# Can-Shield.net
KiCad netlist of a schematic drawn in Altium Designer
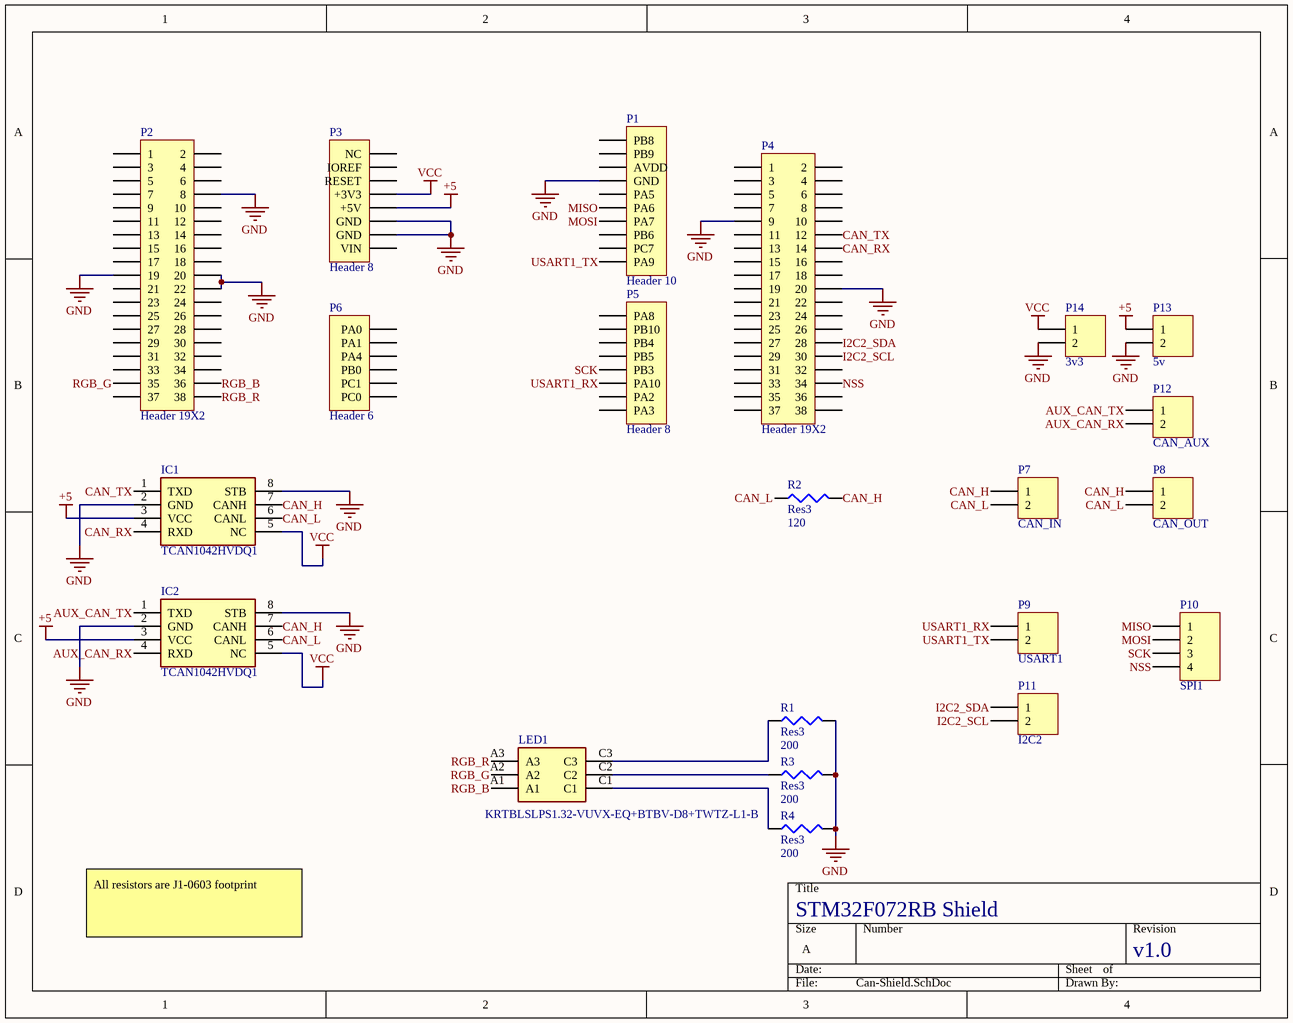
[diagram p0: Can-Shield.SchDoc]

(export (version "E")
  (design (tool "Eeschema 10.0.6"))
  (components
    (comp (ref "IC1")
      (value "TCAN1042HVDQ1")
      (footprint "SamacSys:SOIC127P600X175-8N")
      (description "Integrated Circuit")
      (fields (field (name "MOUSER PART NUMBER") "595-TCAN1042HVDQ1"))
      (libsource (lib "*") (part "TCAN1042HVDQ1"))
    )
    (comp (ref "IC2")
      (value "TCAN1042HVDQ1")
      (footprint "SamacSys:SOIC127P600X175-8N")
      (description "Integrated Circuit")
      (fields (field (name "MOUSER PART NUMBER") "595-TCAN1042HVDQ1"))
      (libsource (lib "*") (part "TCAN1042HVDQ1"))
    )
    (comp (ref "LED1")
      (value "KRTBLSLPS1.32-VUVX-EQ+BTBV-D8+TWTZ-L1-B")
      (footprint "SamacSys:KRTBLSLPS132VUVXEQBTBVD8TWTZL1B")
      (description "LED")
      (fields (field (name "MOUSER PART NUMBER") "720-KRTBLSLPS13A0062"))
      (libsource (lib "*") (part "KRTBLSLPS1.32-VUVX-EQ+BTBV-D8+TWTZ-L1-B"))
    )
    (comp (ref "P1")
      (value "Header 10")
      (footprint "HDR1X10")
      (description "Header, 10-Pin")
      (fields (field (name "PUBLISHER") "Altium Limited"))
      (libsource (lib "Miscellaneous Connectors") (part "Header 10"))
    )
    (comp (ref "P2")
      (value "Header 19X2")
      (footprint "HDR2X19")
      (description "Header, 19-Pin, Dual row")
      (fields (field (name "PUBLISHER") "Altium Limited"))
      (libsource (lib "Miscellaneous Connectors") (part "Header 19X2"))
    )
    (comp (ref "P3")
      (value "Header 8")
      (footprint "HDR1X8")
      (description "Header, 8-Pin")
      (fields (field (name "PUBLISHER") "Altium Limited"))
      (libsource (lib "Miscellaneous Connectors") (part "Header 8"))
    )
    (comp (ref "P4")
      (value "Header 19X2")
      (footprint "HDR2X19")
      (description "Header, 19-Pin, Dual row")
      (fields (field (name "PUBLISHER") "Altium Limited"))
      (libsource (lib "Miscellaneous Connectors") (part "Header 19X2"))
    )
    (comp (ref "P5")
      (value "Header 8")
      (footprint "HDR1X8")
      (description "Header, 8-Pin")
      (fields (field (name "PUBLISHER") "Altium Limited"))
      (libsource (lib "") (part "Header 8_1"))
    )
    (comp (ref "P6")
      (value "Header 6")
      (footprint "HDR1X6")
      (description "Header, 6-Pin")
      (fields (field (name "PUBLISHER") "Altium Limited"))
      (libsource (lib "Miscellaneous Connectors") (part "Header 6"))
    )
    (comp (ref "P7")
      (value "CAN_IN")
      (footprint "HDR1X2")
      (description "Header, 2-Pin")
      (fields (field (name "PUBLISHER") "Altium Limited"))
      (libsource (lib "Miscellaneous Connectors") (part "Header 2"))
    )
    (comp (ref "P8")
      (value "CAN_OUT")
      (footprint "HDR1X2")
      (description "Header, 2-Pin")
      (fields (field (name "PUBLISHER") "Altium Limited"))
      (libsource (lib "Miscellaneous Connectors") (part "Header 2"))
    )
    (comp (ref "P9")
      (value "USART1")
      (footprint "HDR1X2")
      (description "Header, 2-Pin")
      (fields (field (name "PUBLISHER") "Altium Limited"))
      (libsource (lib "Miscellaneous Connectors") (part "Header 2"))
    )
    (comp (ref "P10")
      (value "SPI1")
      (footprint "HDR1X4")
      (description "Header, 4-Pin")
      (fields (field (name "PUBLISHER") "Altium Limited"))
      (libsource (lib "Miscellaneous Connectors") (part "Header 4"))
    )
    (comp (ref "P11")
      (value "I2C2")
      (footprint "HDR1X2")
      (description "Header, 2-Pin")
      (fields (field (name "PUBLISHER") "Altium Limited"))
      (libsource (lib "Miscellaneous Connectors") (part "Header 2"))
    )
    (comp (ref "P12")
      (value "CAN_AUX")
      (footprint "HDR1X2")
      (description "Header, 2-Pin")
      (fields (field (name "PUBLISHER") "Altium Limited"))
      (libsource (lib "Miscellaneous Connectors") (part "Header 2"))
    )
    (comp (ref "P13")
      (value "5v")
      (footprint "HDR1X2")
      (description "Header, 2-Pin")
      (fields (field (name "PUBLISHER") "Altium Limited"))
      (libsource (lib "Miscellaneous Connectors") (part "Header 2"))
    )
    (comp (ref "P14")
      (value "3v3")
      (footprint "HDR1X2")
      (description "Header, 2-Pin")
      (fields (field (name "PUBLISHER") "Altium Limited"))
      (libsource (lib "Miscellaneous Connectors") (part "Header 2"))
    )
    (comp (ref "R1")
      (value "Res3")
      (footprint "J1-0603")
      (description "Resistor")
      (fields (field (name "ALTIUM_VALUE") "200") (field (name "PUBLISHER") "Altium Limited"))
      (libsource (lib "Miscellaneous Devices") (part "Res3"))
    )
    (comp (ref "R2")
      (value "Res3")
      (footprint "J1-0603")
      (description "Resistor")
      (fields (field (name "ALTIUM_VALUE") "120") (field (name "PUBLISHER") "Altium Limited"))
      (libsource (lib "Miscellaneous Devices") (part "Res3"))
    )
    (comp (ref "R3")
      (value "Res3")
      (footprint "J1-0603")
      (description "Resistor")
      (fields (field (name "ALTIUM_VALUE") "200") (field (name "PUBLISHER") "Altium Limited"))
      (libsource (lib "Miscellaneous Devices") (part "Res3"))
    )
    (comp (ref "R4")
      (value "Res3")
      (footprint "J1-0603")
      (description "Resistor")
      (fields (field (name "ALTIUM_VALUE") "200") (field (name "PUBLISHER") "Altium Limited"))
      (libsource (lib "Miscellaneous Devices") (part "Res3"))
    )
  )
  (nets
    (net (code "1") (name "+5") (class "Default")
      (node (ref "IC1") (pin "3") (pinfunction "VCC_3") (pintype "passive"))
      (node (ref "IC2") (pin "3") (pinfunction "VCC_3") (pintype "passive"))
      (node (ref "P13") (pin "1") (pinfunction "1_1") (pintype "passive"))
      (node (ref "P3") (pin "5") (pinfunction "+5V_5") (pintype "passive"))
    )
    (net (code "2") (name "/AUX_CAN_RX") (class "Default")
      (node (ref "IC2") (pin "4") (pinfunction "RXD_4") (pintype "passive"))
      (node (ref "P12") (pin "2") (pinfunction "2_2") (pintype "passive"))
    )
    (net (code "3") (name "/AUX_CAN_TX") (class "Default")
      (node (ref "IC2") (pin "1") (pinfunction "TXD_1") (pintype "passive"))
      (node (ref "P12") (pin "1") (pinfunction "1_1") (pintype "passive"))
    )
    (net (code "4") (name "/CAN_H") (class "Default")
      (node (ref "IC1") (pin "7") (pinfunction "CANH_7") (pintype "passive"))
      (node (ref "IC2") (pin "7") (pinfunction "CANH_7") (pintype "passive"))
      (node (ref "P7") (pin "1") (pinfunction "1_1") (pintype "passive"))
      (node (ref "P8") (pin "1") (pinfunction "1_1") (pintype "passive"))
      (node (ref "R2") (pin "2") (pinfunction "2_2") (pintype "passive"))
    )
    (net (code "5") (name "/CAN_L") (class "Default")
      (node (ref "IC1") (pin "6") (pinfunction "CANL_6") (pintype "passive"))
      (node (ref "IC2") (pin "6") (pinfunction "CANL_6") (pintype "passive"))
      (node (ref "P7") (pin "2") (pinfunction "2_2") (pintype "passive"))
      (node (ref "P8") (pin "2") (pinfunction "2_2") (pintype "passive"))
      (node (ref "R2") (pin "1") (pinfunction "1_1") (pintype "passive"))
    )
    (net (code "6") (name "/CAN_RX") (class "Default")
      (node (ref "IC1") (pin "4") (pinfunction "RXD_4") (pintype "passive"))
      (node (ref "P4") (pin "14") (pinfunction "14_14") (pintype "passive"))
    )
    (net (code "7") (name "/CAN_TX") (class "Default")
      (node (ref "IC1") (pin "1") (pinfunction "TXD_1") (pintype "passive"))
      (node (ref "P4") (pin "12") (pinfunction "12_12") (pintype "passive"))
    )
    (net (code "8") (name "/I2C2_SCL") (class "Default")
      (node (ref "P11") (pin "2") (pinfunction "2_2") (pintype "passive"))
      (node (ref "P4") (pin "30") (pinfunction "30_30") (pintype "passive"))
    )
    (net (code "9") (name "/I2C2_SDA") (class "Default")
      (node (ref "P11") (pin "1") (pinfunction "1_1") (pintype "passive"))
      (node (ref "P4") (pin "28") (pinfunction "28_28") (pintype "passive"))
    )
    (net (code "10") (name "/MISO") (class "Default")
      (node (ref "P1") (pin "6") (pinfunction "PA6_6") (pintype "passive"))
      (node (ref "P10") (pin "1") (pinfunction "1_1") (pintype "passive"))
    )
    (net (code "11") (name "/MOSI") (class "Default")
      (node (ref "P1") (pin "7") (pinfunction "PA7_7") (pintype "passive"))
      (node (ref "P10") (pin "2") (pinfunction "2_2") (pintype "passive"))
    )
    (net (code "12") (name "/NSS") (class "Default")
      (node (ref "P10") (pin "4") (pinfunction "4_4") (pintype "passive"))
      (node (ref "P4") (pin "34") (pinfunction "34_34") (pintype "passive"))
    )
    (net (code "13") (name "/RGB_B") (class "Default")
      (node (ref "LED1") (pin "A1") (pinfunction "A1_A1") (pintype "passive"))
      (node (ref "P2") (pin "36") (pinfunction "36_36") (pintype "passive"))
    )
    (net (code "14") (name "/RGB_G") (class "Default")
      (node (ref "LED1") (pin "A2") (pinfunction "A2_A2") (pintype "passive"))
      (node (ref "P2") (pin "35") (pinfunction "35_35") (pintype "passive"))
    )
    (net (code "15") (name "/RGB_R") (class "Default")
      (node (ref "LED1") (pin "A3") (pinfunction "A3_A3") (pintype "passive"))
      (node (ref "P2") (pin "38") (pinfunction "38_38") (pintype "passive"))
    )
    (net (code "16") (name "/SCK") (class "Default")
      (node (ref "P10") (pin "3") (pinfunction "3_3") (pintype "passive"))
      (node (ref "P5") (pin "5") (pinfunction "PB3_5") (pintype "passive"))
    )
    (net (code "17") (name "/USART1_RX") (class "Default")
      (node (ref "P5") (pin "6") (pinfunction "PA10_6") (pintype "passive"))
      (node (ref "P9") (pin "1") (pinfunction "1_1") (pintype "passive"))
    )
    (net (code "18") (name "/USART1_TX") (class "Default")
      (node (ref "P1") (pin "10") (pinfunction "PA9_10") (pintype "passive"))
      (node (ref "P9") (pin "2") (pinfunction "2_2") (pintype "passive"))
    )
    (net (code "19") (name "GND") (class "Default")
      (node (ref "IC1") (pin "2") (pinfunction "GND_2") (pintype "passive"))
      (node (ref "IC1") (pin "8") (pinfunction "STB_8") (pintype "passive"))
      (node (ref "IC2") (pin "2") (pinfunction "GND_2") (pintype "passive"))
      (node (ref "IC2") (pin "8") (pinfunction "STB_8") (pintype "passive"))
      (node (ref "P1") (pin "4") (pinfunction "GND_4") (pintype "passive"))
      (node (ref "P13") (pin "2") (pinfunction "2_2") (pintype "passive"))
      (node (ref "P14") (pin "2") (pinfunction "2_2") (pintype "passive"))
      (node (ref "P2") (pin "19") (pinfunction "19_19") (pintype "passive"))
      (node (ref "P2") (pin "20") (pinfunction "20_20") (pintype "passive"))
      (node (ref "P2") (pin "22") (pinfunction "22_22") (pintype "passive"))
      (node (ref "P2") (pin "8") (pinfunction "8_8") (pintype "passive"))
      (node (ref "P3") (pin "6") (pinfunction "GND_6") (pintype "passive"))
      (node (ref "P3") (pin "7") (pinfunction "GND_7") (pintype "passive"))
      (node (ref "P4") (pin "20") (pinfunction "20_20") (pintype "passive"))
      (node (ref "P4") (pin "9") (pinfunction "9_9") (pintype "passive"))
      (node (ref "R1") (pin "2") (pinfunction "2_2") (pintype "passive"))
      (node (ref "R3") (pin "2") (pinfunction "2_2") (pintype "passive"))
      (node (ref "R4") (pin "2") (pinfunction "2_2") (pintype "passive"))
    )
    (net (code "20") (name "Net-(LED1-PadC1)") (class "Default")
      (node (ref "LED1") (pin "C1") (pinfunction "C1_C1") (pintype "passive"))
      (node (ref "R4") (pin "1") (pinfunction "1_1") (pintype "passive"))
    )
    (net (code "21") (name "Net-(LED1-PadC2)") (class "Default")
      (node (ref "LED1") (pin "C2") (pinfunction "C2_C2") (pintype "passive"))
      (node (ref "R3") (pin "1") (pinfunction "1_1") (pintype "passive"))
    )
    (net (code "22") (name "Net-(LED1-PadC3)") (class "Default")
      (node (ref "LED1") (pin "C3") (pinfunction "C3_C3") (pintype "passive"))
      (node (ref "R1") (pin "1") (pinfunction "1_1") (pintype "passive"))
    )
    (net (code "23") (name "VCC") (class "Default")
      (node (ref "IC1") (pin "5") (pinfunction "NC_5") (pintype "passive"))
      (node (ref "IC2") (pin "5") (pinfunction "NC_5") (pintype "passive"))
      (node (ref "P14") (pin "1") (pinfunction "1_1") (pintype "passive"))
      (node (ref "P3") (pin "4") (pinfunction "+3V3_4") (pintype "passive"))
    )
    (net (code "24") (name "unconnected-(P1-AVDD-Pad3)") (class "Default")
      (node (ref "P1") (pin "3") (pinfunction "AVDD_3") (pintype "passive"))
    )
    (net (code "25") (name "unconnected-(P1-PA5-Pad5)") (class "Default")
      (node (ref "P1") (pin "5") (pinfunction "PA5_5") (pintype "passive"))
    )
    (net (code "26") (name "unconnected-(P1-PB6-Pad8)") (class "Default")
      (node (ref "P1") (pin "8") (pinfunction "PB6_8") (pintype "passive"))
    )
    (net (code "27") (name "unconnected-(P1-PB8-Pad1)") (class "Default")
      (node (ref "P1") (pin "1") (pinfunction "PB8_1") (pintype "passive"))
    )
    (net (code "28") (name "unconnected-(P1-PB9-Pad2)") (class "Default")
      (node (ref "P1") (pin "2") (pinfunction "PB9_2") (pintype "passive"))
    )
    (net (code "29") (name "unconnected-(P1-PC7-Pad9)") (class "Default")
      (node (ref "P1") (pin "9") (pinfunction "PC7_9") (pintype "passive"))
    )
    (net (code "30") (name "unconnected-(P2-Pad1)") (class "Default")
      (node (ref "P2") (pin "1") (pinfunction "1_1") (pintype "passive"))
    )
    (net (code "31") (name "unconnected-(P2-Pad2)") (class "Default")
      (node (ref "P2") (pin "2") (pinfunction "2_2") (pintype "passive"))
    )
    (net (code "32") (name "unconnected-(P2-Pad3)") (class "Default")
      (node (ref "P2") (pin "3") (pinfunction "3_3") (pintype "passive"))
    )
    (net (code "33") (name "unconnected-(P2-Pad4)") (class "Default")
      (node (ref "P2") (pin "4") (pinfunction "4_4") (pintype "passive"))
    )
    (net (code "34") (name "unconnected-(P2-Pad5)") (class "Default")
      (node (ref "P2") (pin "5") (pinfunction "5_5") (pintype "passive"))
    )
    (net (code "35") (name "unconnected-(P2-Pad6)") (class "Default")
      (node (ref "P2") (pin "6") (pinfunction "6_6") (pintype "passive"))
    )
    (net (code "36") (name "unconnected-(P2-Pad7)") (class "Default")
      (node (ref "P2") (pin "7") (pinfunction "7_7") (pintype "passive"))
    )
    (net (code "37") (name "unconnected-(P2-Pad9)") (class "Default")
      (node (ref "P2") (pin "9") (pinfunction "9_9") (pintype "passive"))
    )
    (net (code "38") (name "unconnected-(P2-Pad10)") (class "Default")
      (node (ref "P2") (pin "10") (pinfunction "10_10") (pintype "passive"))
    )
    (net (code "39") (name "unconnected-(P2-Pad11)") (class "Default")
      (node (ref "P2") (pin "11") (pinfunction "11_11") (pintype "passive"))
    )
    (net (code "40") (name "unconnected-(P2-Pad12)") (class "Default")
      (node (ref "P2") (pin "12") (pinfunction "12_12") (pintype "passive"))
    )
    (net (code "41") (name "unconnected-(P2-Pad13)") (class "Default")
      (node (ref "P2") (pin "13") (pinfunction "13_13") (pintype "passive"))
    )
    (net (code "42") (name "unconnected-(P2-Pad14)") (class "Default")
      (node (ref "P2") (pin "14") (pinfunction "14_14") (pintype "passive"))
    )
    (net (code "43") (name "unconnected-(P2-Pad15)") (class "Default")
      (node (ref "P2") (pin "15") (pinfunction "15_15") (pintype "passive"))
    )
    (net (code "44") (name "unconnected-(P2-Pad16)") (class "Default")
      (node (ref "P2") (pin "16") (pinfunction "16_16") (pintype "passive"))
    )
    (net (code "45") (name "unconnected-(P2-Pad17)") (class "Default")
      (node (ref "P2") (pin "17") (pinfunction "17_17") (pintype "passive"))
    )
    (net (code "46") (name "unconnected-(P2-Pad18)") (class "Default")
      (node (ref "P2") (pin "18") (pinfunction "18_18") (pintype "passive"))
    )
    (net (code "47") (name "unconnected-(P2-Pad21)") (class "Default")
      (node (ref "P2") (pin "21") (pinfunction "21_21") (pintype "passive"))
    )
    (net (code "48") (name "unconnected-(P2-Pad23)") (class "Default")
      (node (ref "P2") (pin "23") (pinfunction "23_23") (pintype "passive"))
    )
    (net (code "49") (name "unconnected-(P2-Pad24)") (class "Default")
      (node (ref "P2") (pin "24") (pinfunction "24_24") (pintype "passive"))
    )
    (net (code "50") (name "unconnected-(P2-Pad25)") (class "Default")
      (node (ref "P2") (pin "25") (pinfunction "25_25") (pintype "passive"))
    )
    (net (code "51") (name "unconnected-(P2-Pad26)") (class "Default")
      (node (ref "P2") (pin "26") (pinfunction "26_26") (pintype "passive"))
    )
    (net (code "52") (name "unconnected-(P2-Pad27)") (class "Default")
      (node (ref "P2") (pin "27") (pinfunction "27_27") (pintype "passive"))
    )
    (net (code "53") (name "unconnected-(P2-Pad28)") (class "Default")
      (node (ref "P2") (pin "28") (pinfunction "28_28") (pintype "passive"))
    )
    (net (code "54") (name "unconnected-(P2-Pad29)") (class "Default")
      (node (ref "P2") (pin "29") (pinfunction "29_29") (pintype "passive"))
    )
    (net (code "55") (name "unconnected-(P2-Pad30)") (class "Default")
      (node (ref "P2") (pin "30") (pinfunction "30_30") (pintype "passive"))
    )
    (net (code "56") (name "unconnected-(P2-Pad31)") (class "Default")
      (node (ref "P2") (pin "31") (pinfunction "31_31") (pintype "passive"))
    )
    (net (code "57") (name "unconnected-(P2-Pad32)") (class "Default")
      (node (ref "P2") (pin "32") (pinfunction "32_32") (pintype "passive"))
    )
    (net (code "58") (name "unconnected-(P2-Pad33)") (class "Default")
      (node (ref "P2") (pin "33") (pinfunction "33_33") (pintype "passive"))
    )
    (net (code "59") (name "unconnected-(P2-Pad34)") (class "Default")
      (node (ref "P2") (pin "34") (pinfunction "34_34") (pintype "passive"))
    )
    (net (code "60") (name "unconnected-(P2-Pad37)") (class "Default")
      (node (ref "P2") (pin "37") (pinfunction "37_37") (pintype "passive"))
    )
    (net (code "61") (name "unconnected-(P3-IOREF-Pad2)") (class "Default")
      (node (ref "P3") (pin "2") (pinfunction "IOREF_2") (pintype "passive"))
    )
    (net (code "62") (name "unconnected-(P3-NC-Pad1)") (class "Default")
      (node (ref "P3") (pin "1") (pinfunction "NC_1") (pintype "passive"))
    )
    (net (code "63") (name "unconnected-(P3-RESET-Pad3)") (class "Default")
      (node (ref "P3") (pin "3") (pinfunction "RESET_3") (pintype "passive"))
    )
    (net (code "64") (name "unconnected-(P3-VIN-Pad8)") (class "Default")
      (node (ref "P3") (pin "8") (pinfunction "VIN_8") (pintype "passive"))
    )
    (net (code "65") (name "unconnected-(P4-Pad1)") (class "Default")
      (node (ref "P4") (pin "1") (pinfunction "1_1") (pintype "passive"))
    )
    (net (code "66") (name "unconnected-(P4-Pad2)") (class "Default")
      (node (ref "P4") (pin "2") (pinfunction "2_2") (pintype "passive"))
    )
    (net (code "67") (name "unconnected-(P4-Pad3)") (class "Default")
      (node (ref "P4") (pin "3") (pinfunction "3_3") (pintype "passive"))
    )
    (net (code "68") (name "unconnected-(P4-Pad4)") (class "Default")
      (node (ref "P4") (pin "4") (pinfunction "4_4") (pintype "passive"))
    )
    (net (code "69") (name "unconnected-(P4-Pad5)") (class "Default")
      (node (ref "P4") (pin "5") (pinfunction "5_5") (pintype "passive"))
    )
    (net (code "70") (name "unconnected-(P4-Pad6)") (class "Default")
      (node (ref "P4") (pin "6") (pinfunction "6_6") (pintype "passive"))
    )
    (net (code "71") (name "unconnected-(P4-Pad7)") (class "Default")
      (node (ref "P4") (pin "7") (pinfunction "7_7") (pintype "passive"))
    )
    (net (code "72") (name "unconnected-(P4-Pad8)") (class "Default")
      (node (ref "P4") (pin "8") (pinfunction "8_8") (pintype "passive"))
    )
    (net (code "73") (name "unconnected-(P4-Pad10)") (class "Default")
      (node (ref "P4") (pin "10") (pinfunction "10_10") (pintype "passive"))
    )
    (net (code "74") (name "unconnected-(P4-Pad11)") (class "Default")
      (node (ref "P4") (pin "11") (pinfunction "11_11") (pintype "passive"))
    )
    (net (code "75") (name "unconnected-(P4-Pad13)") (class "Default")
      (node (ref "P4") (pin "13") (pinfunction "13_13") (pintype "passive"))
    )
    (net (code "76") (name "unconnected-(P4-Pad15)") (class "Default")
      (node (ref "P4") (pin "15") (pinfunction "15_15") (pintype "passive"))
    )
    (net (code "77") (name "unconnected-(P4-Pad16)") (class "Default")
      (node (ref "P4") (pin "16") (pinfunction "16_16") (pintype "passive"))
    )
    (net (code "78") (name "unconnected-(P4-Pad17)") (class "Default")
      (node (ref "P4") (pin "17") (pinfunction "17_17") (pintype "passive"))
    )
    (net (code "79") (name "unconnected-(P4-Pad18)") (class "Default")
      (node (ref "P4") (pin "18") (pinfunction "18_18") (pintype "passive"))
    )
    (net (code "80") (name "unconnected-(P4-Pad19)") (class "Default")
      (node (ref "P4") (pin "19") (pinfunction "19_19") (pintype "passive"))
    )
    (net (code "81") (name "unconnected-(P4-Pad21)") (class "Default")
      (node (ref "P4") (pin "21") (pinfunction "21_21") (pintype "passive"))
    )
    (net (code "82") (name "unconnected-(P4-Pad22)") (class "Default")
      (node (ref "P4") (pin "22") (pinfunction "22_22") (pintype "passive"))
    )
    (net (code "83") (name "unconnected-(P4-Pad23)") (class "Default")
      (node (ref "P4") (pin "23") (pinfunction "23_23") (pintype "passive"))
    )
    (net (code "84") (name "unconnected-(P4-Pad24)") (class "Default")
      (node (ref "P4") (pin "24") (pinfunction "24_24") (pintype "passive"))
    )
    (net (code "85") (name "unconnected-(P4-Pad25)") (class "Default")
      (node (ref "P4") (pin "25") (pinfunction "25_25") (pintype "passive"))
    )
    (net (code "86") (name "unconnected-(P4-Pad26)") (class "Default")
      (node (ref "P4") (pin "26") (pinfunction "26_26") (pintype "passive"))
    )
    (net (code "87") (name "unconnected-(P4-Pad27)") (class "Default")
      (node (ref "P4") (pin "27") (pinfunction "27_27") (pintype "passive"))
    )
    (net (code "88") (name "unconnected-(P4-Pad29)") (class "Default")
      (node (ref "P4") (pin "29") (pinfunction "29_29") (pintype "passive"))
    )
    (net (code "89") (name "unconnected-(P4-Pad31)") (class "Default")
      (node (ref "P4") (pin "31") (pinfunction "31_31") (pintype "passive"))
    )
    (net (code "90") (name "unconnected-(P4-Pad32)") (class "Default")
      (node (ref "P4") (pin "32") (pinfunction "32_32") (pintype "passive"))
    )
    (net (code "91") (name "unconnected-(P4-Pad33)") (class "Default")
      (node (ref "P4") (pin "33") (pinfunction "33_33") (pintype "passive"))
    )
    (net (code "92") (name "unconnected-(P4-Pad35)") (class "Default")
      (node (ref "P4") (pin "35") (pinfunction "35_35") (pintype "passive"))
    )
    (net (code "93") (name "unconnected-(P4-Pad36)") (class "Default")
      (node (ref "P4") (pin "36") (pinfunction "36_36") (pintype "passive"))
    )
    (net (code "94") (name "unconnected-(P4-Pad37)") (class "Default")
      (node (ref "P4") (pin "37") (pinfunction "37_37") (pintype "passive"))
    )
    (net (code "95") (name "unconnected-(P4-Pad38)") (class "Default")
      (node (ref "P4") (pin "38") (pinfunction "38_38") (pintype "passive"))
    )
    (net (code "96") (name "unconnected-(P5-PA2-Pad7)") (class "Default")
      (node (ref "P5") (pin "7") (pinfunction "PA2_7") (pintype "passive"))
    )
    (net (code "97") (name "unconnected-(P5-PA3-Pad8)") (class "Default")
      (node (ref "P5") (pin "8") (pinfunction "PA3_8") (pintype "passive"))
    )
    (net (code "98") (name "unconnected-(P5-PA8-Pad1)") (class "Default")
      (node (ref "P5") (pin "1") (pinfunction "PA8_1") (pintype "passive"))
    )
    (net (code "99") (name "unconnected-(P5-PB4-Pad3)") (class "Default")
      (node (ref "P5") (pin "3") (pinfunction "PB4_3") (pintype "passive"))
    )
    (net (code "100") (name "unconnected-(P5-PB5-Pad4)") (class "Default")
      (node (ref "P5") (pin "4") (pinfunction "PB5_4") (pintype "passive"))
    )
    (net (code "101") (name "unconnected-(P5-PB10-Pad2)") (class "Default")
      (node (ref "P5") (pin "2") (pinfunction "PB10_2") (pintype "passive"))
    )
    (net (code "102") (name "unconnected-(P6-PA0-Pad1)") (class "Default")
      (node (ref "P6") (pin "1") (pinfunction "PA0_1") (pintype "passive"))
    )
    (net (code "103") (name "unconnected-(P6-PA1-Pad2)") (class "Default")
      (node (ref "P6") (pin "2") (pinfunction "PA1_2") (pintype "passive"))
    )
    (net (code "104") (name "unconnected-(P6-PA4-Pad3)") (class "Default")
      (node (ref "P6") (pin "3") (pinfunction "PA4_3") (pintype "passive"))
    )
    (net (code "105") (name "unconnected-(P6-PB0-Pad4)") (class "Default")
      (node (ref "P6") (pin "4") (pinfunction "PB0_4") (pintype "passive"))
    )
    (net (code "106") (name "unconnected-(P6-PC0-Pad6)") (class "Default")
      (node (ref "P6") (pin "6") (pinfunction "PC0_6") (pintype "passive"))
    )
    (net (code "107") (name "unconnected-(P6-PC1-Pad5)") (class "Default")
      (node (ref "P6") (pin "5") (pinfunction "PC1_5") (pintype "passive"))
    )
  )
)
